# batteryholder2S3P_revC.net
KiCad netlist of a schematic drawn in EAGLE
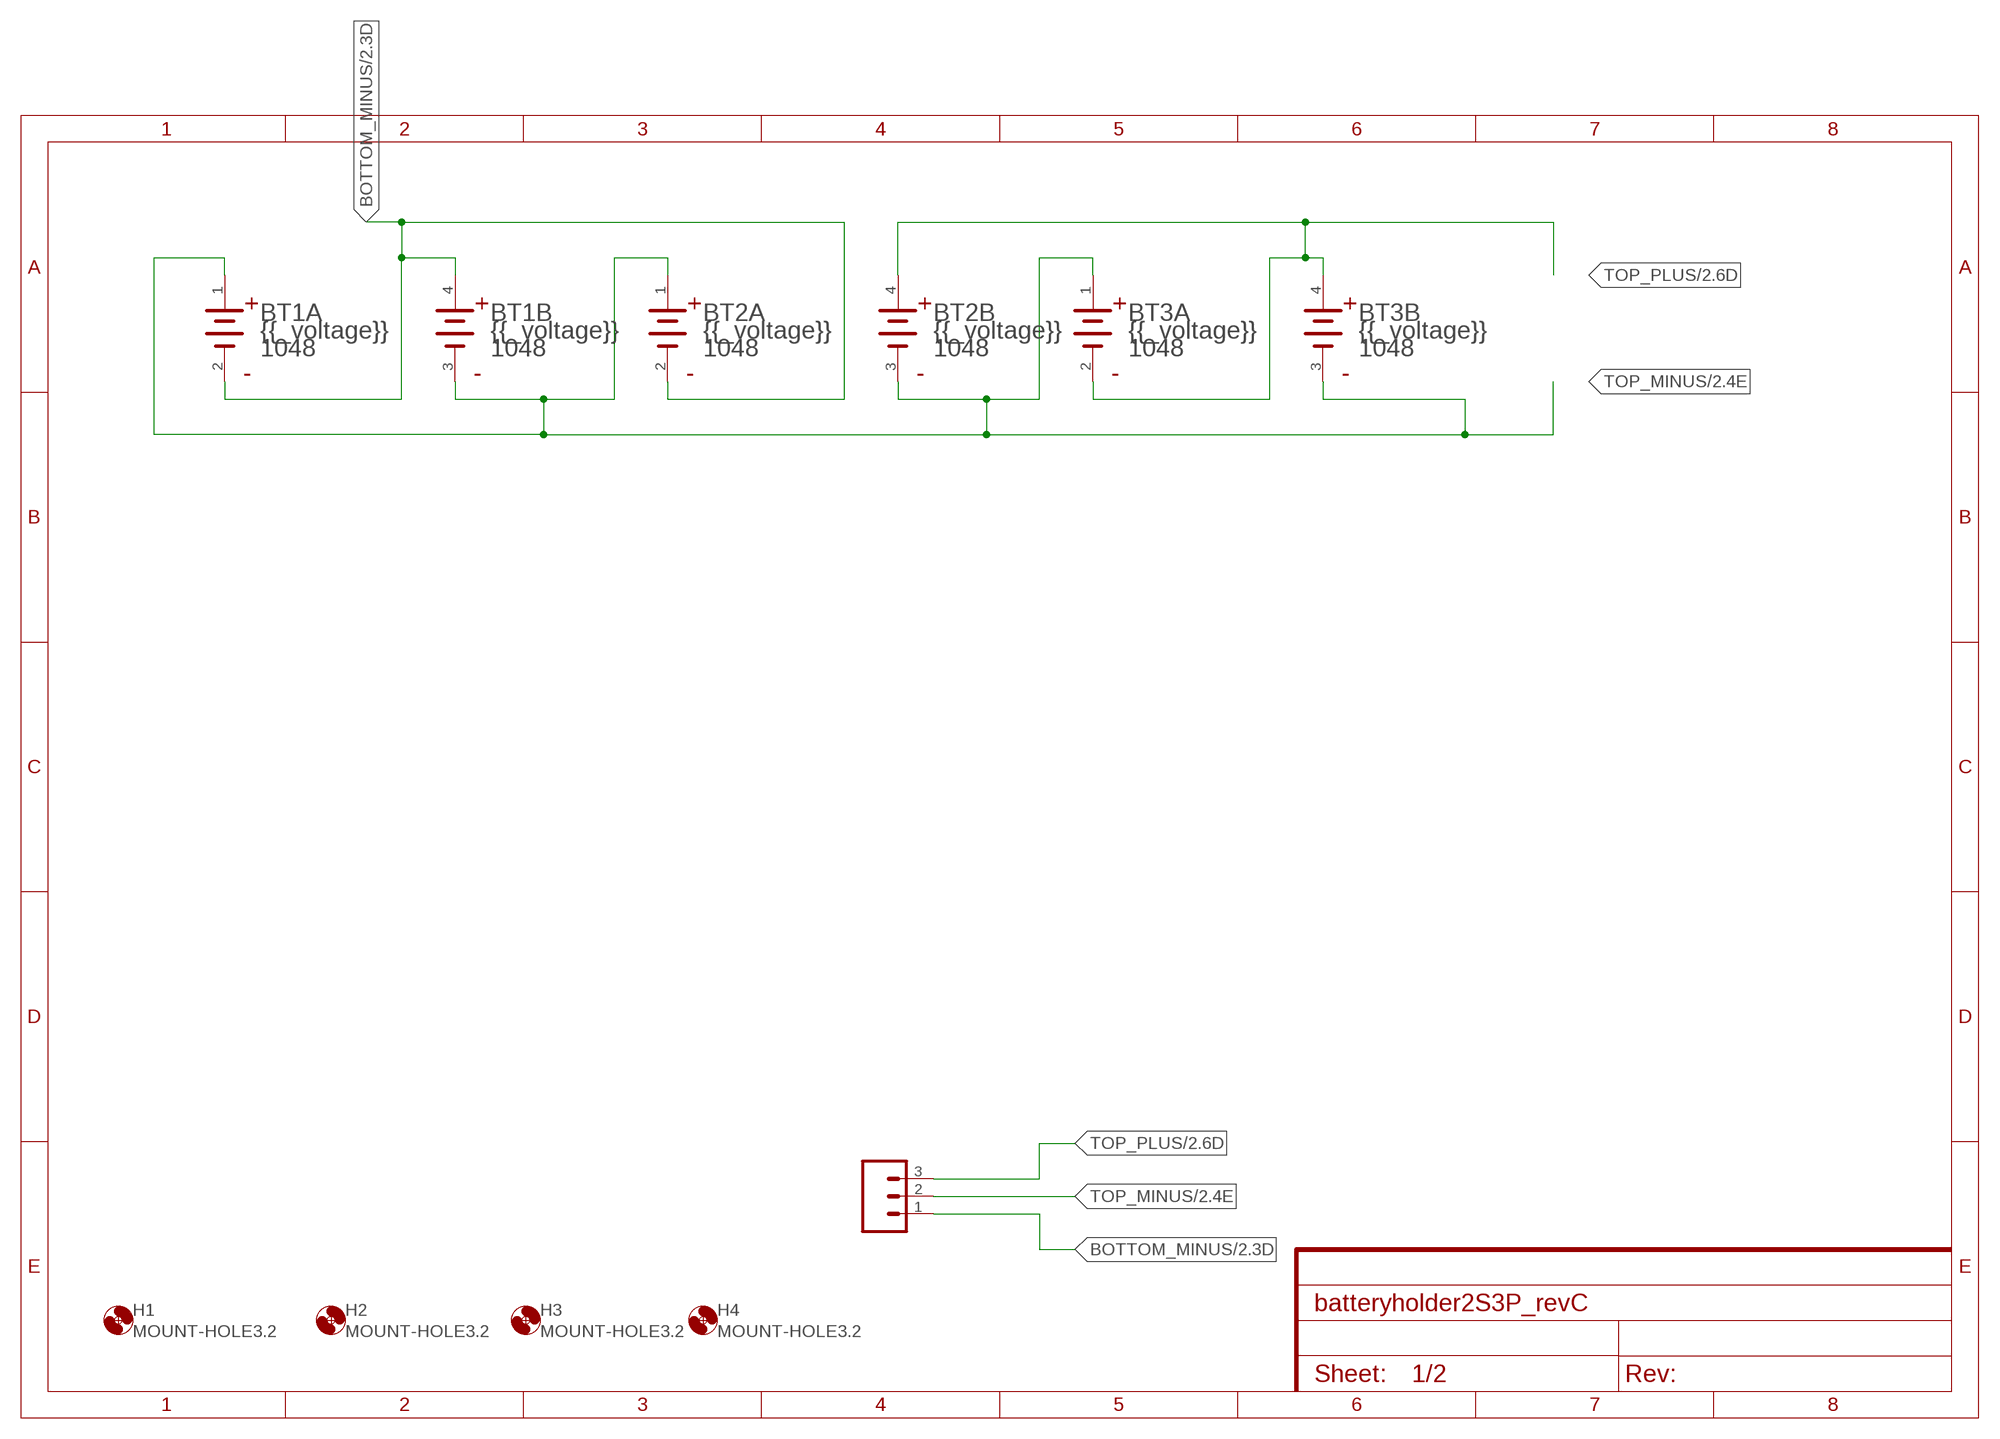
[diagram p0: schematic, sheet 1]
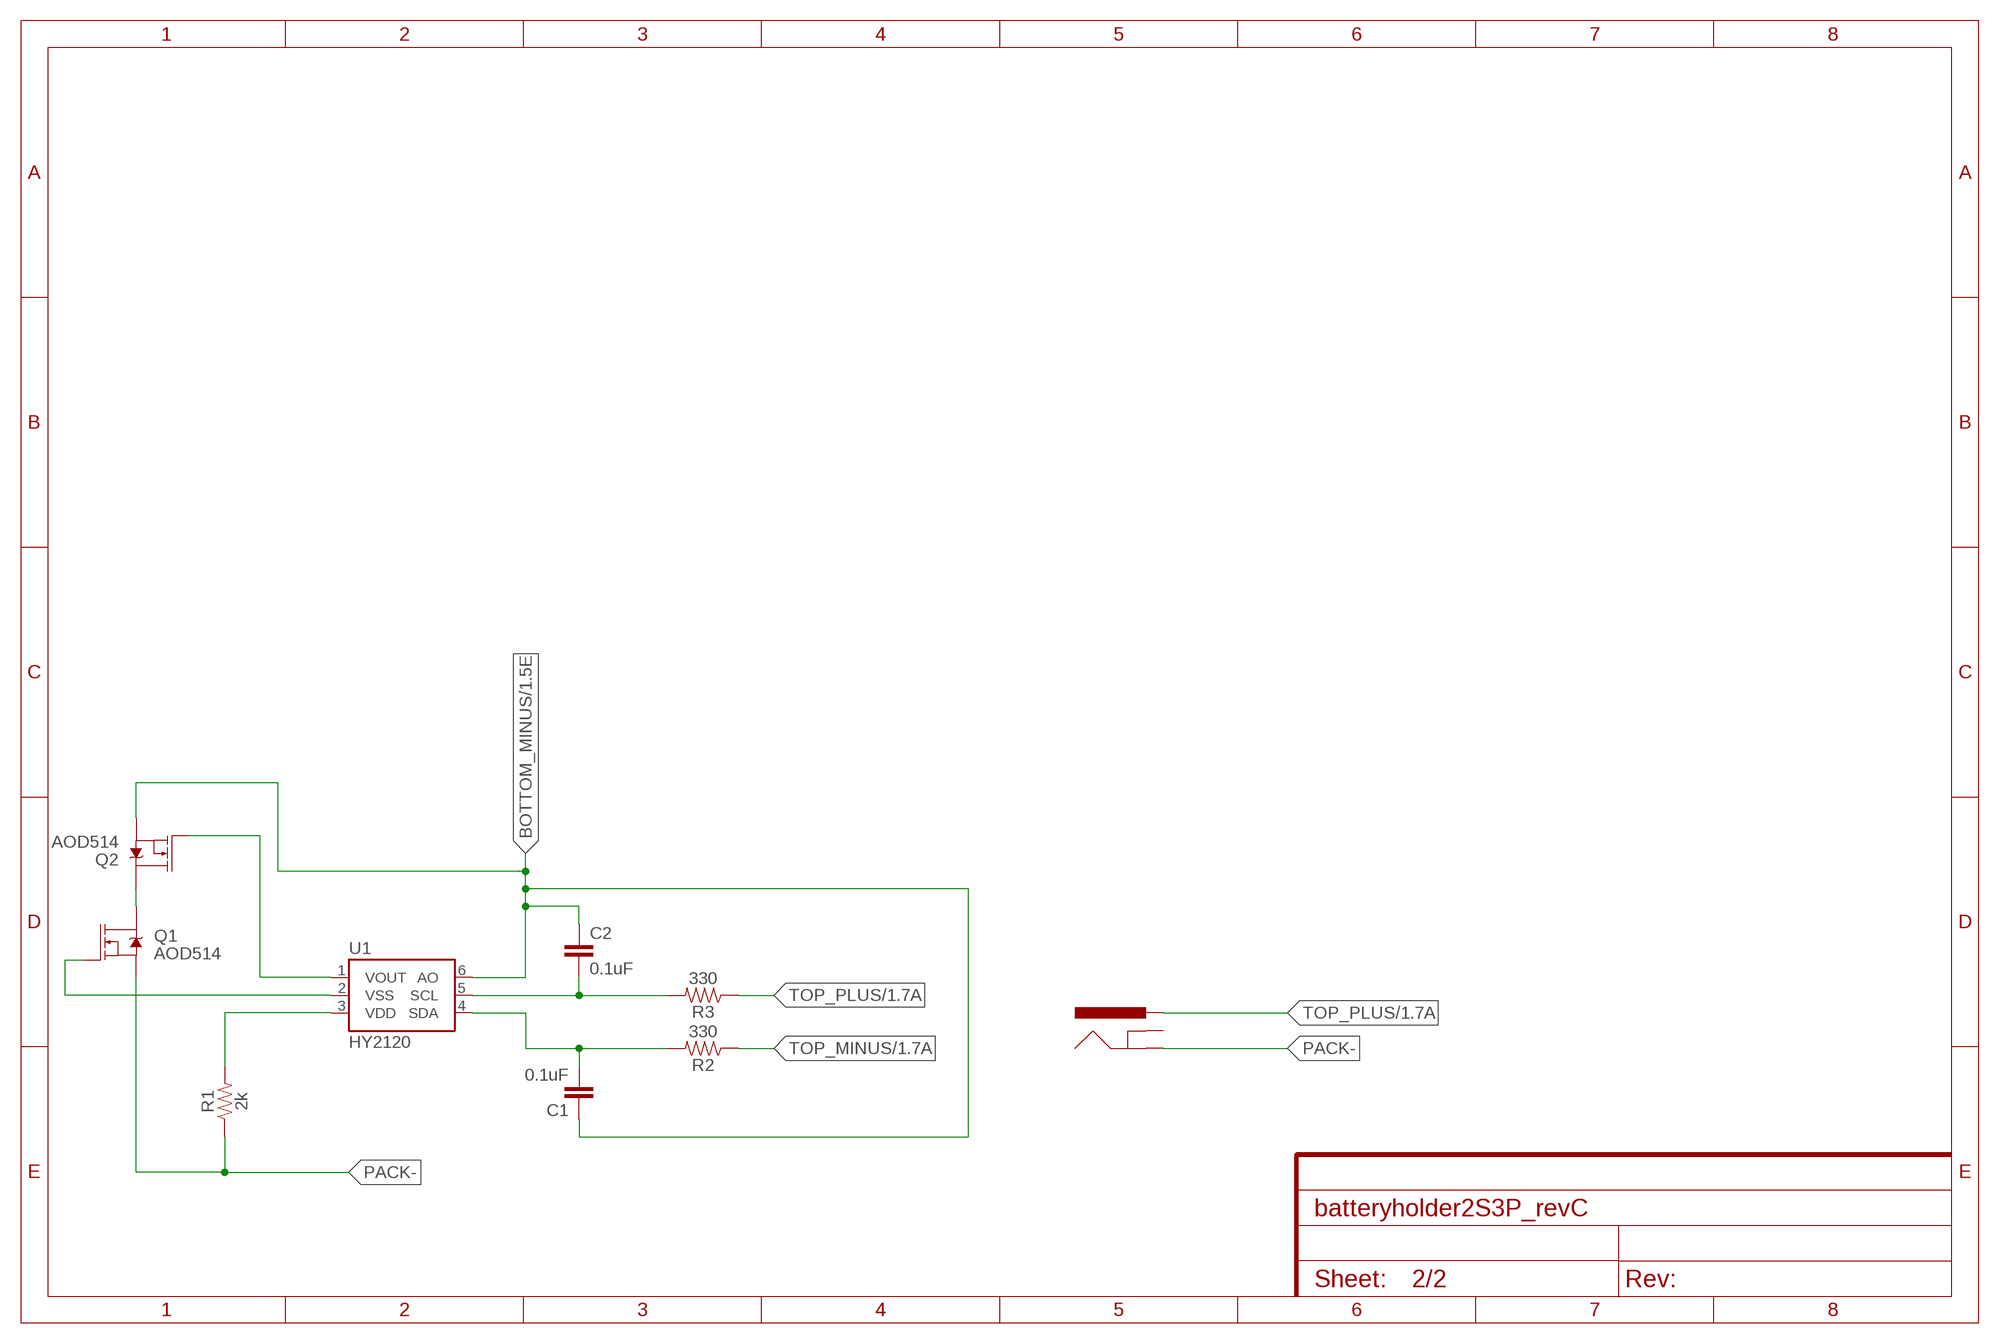
[diagram p1: schematic, sheet 2]

(export (version "E")
  (design (tool "Eeschema 10.0.6"))
  (components
    (comp (ref "C1")
      (value "0.1uF")
      (footprint "eagle-import:1206")
      (libsource (lib "eagle-import") (part "1.0UF-1206-50V-10%"))
    )
    (comp (ref "C2")
      (value "0.1uF")
      (footprint "eagle-import:1206")
      (libsource (lib "eagle-import") (part "1.0UF-1206-50V-10%"))
    )
    (comp (ref "J2")
      (value "POWER_JACKPTH_BREAD")
      (footprint "eagle-import:POWER_JACK_PTH_BREAD")
      (libsource (lib "eagle-import") (part "POWER_JACKPTH_BREAD"))
    )
    (comp (ref "Q1")
      (value "AOD514")
      (footprint "eagle-import:DPAK")
      (libsource (lib "eagle-import") (part "MOSFET-NCH-FDD8780"))
    )
    (comp (ref "Q2")
      (value "AOD514")
      (footprint "eagle-import:DPAK")
      (libsource (lib "eagle-import") (part "MOSFET-NCH-FDD8780"))
    )
    (comp (ref "R1")
      (value "2k")
      (footprint "eagle-import:1206")
      (libsource (lib "eagle-import") (part "RESISTOR1206"))
    )
    (comp (ref "R2")
      (value "330")
      (footprint "eagle-import:1206")
      (libsource (lib "eagle-import") (part "RESISTOR1206"))
    )
    (comp (ref "R3")
      (value "330")
      (footprint "eagle-import:1206")
      (libsource (lib "eagle-import") (part "RESISTOR1206"))
    )
    (comp (ref "U1")
      (value "HY2120")
      (footprint "eagle-import:SOT23-6")
      (libsource (lib "eagle-import") (part "MCP4725SOT-23"))
    )
    (comp (ref "BT1")
      (value "KEYSTONE_1048KEYSTONE_1048_0_0")
      (footprint "eagle-import:KEYSTONE_1048_0")
      (fields
        (field (name "DIGIKEY_PART_NUMBER") "36-1048-ND")
        (field (name "MF") "Keystone")
        (field (name "MOUSER_PART_NUMBER") "534-1048")
      )
      (libsource (lib "eagle-import") (part "KEYSTONE_1048KEYSTONE_1048_0_0"))
    )
    (comp (ref "BT2")
      (value "KEYSTONE_1048KEYSTONE_1048_0_0")
      (footprint "eagle-import:KEYSTONE_1048_0")
      (fields
        (field (name "DIGIKEY_PART_NUMBER") "36-1048-ND")
        (field (name "MF") "Keystone")
        (field (name "MOUSER_PART_NUMBER") "534-1048")
      )
      (libsource (lib "eagle-import") (part "KEYSTONE_1048KEYSTONE_1048_0_0"))
    )
    (comp (ref "BT3")
      (value "KEYSTONE_1048KEYSTONE_1048_0_0")
      (footprint "eagle-import:KEYSTONE_1048_0")
      (fields
        (field (name "DIGIKEY_PART_NUMBER") "36-1048-ND")
        (field (name "MF") "Keystone")
        (field (name "MOUSER_PART_NUMBER") "534-1048")
      )
      (libsource (lib "eagle-import") (part "KEYSTONE_1048KEYSTONE_1048_0_0"))
    )
    (comp (ref "H1")
      (value "MOUNT-HOLE3.2")
      (footprint "eagle-import:3,2")
      (libsource (lib "eagle-import") (part "MOUNT-HOLE3.2"))
    )
    (comp (ref "H2")
      (value "MOUNT-HOLE3.2")
      (footprint "eagle-import:3,2")
      (libsource (lib "eagle-import") (part "MOUNT-HOLE3.2"))
    )
    (comp (ref "H3")
      (value "MOUNT-HOLE3.2")
      (footprint "eagle-import:3,2")
      (libsource (lib "eagle-import") (part "MOUNT-HOLE3.2"))
    )
    (comp (ref "H4")
      (value "MOUNT-HOLE3.2")
      (footprint "eagle-import:3,2")
      (libsource (lib "eagle-import") (part "MOUNT-HOLE3.2"))
    )
    (comp (ref "J1")
      (value "CONN_03-SCREW-5MM")
      (footprint "eagle-import:SCREWTERMINAL-5MM-3")
      (libsource (lib "eagle-import") (part "CONN_03-SCREW-5MM"))
    )
  )
  (nets
    (net (code "1") (name "BOTTOM_MINUS") (class "Default")
      (node (ref "BT1") (pin "2") (pinfunction "1_CATHODE_2") (pintype "passive"))
      (node (ref "BT1") (pin "4") (pinfunction "2_ANODE_4") (pintype "passive"))
      (node (ref "BT2") (pin "2") (pinfunction "1_CATHODE_2") (pintype "passive"))
      (node (ref "C1") (pin "1") (pinfunction "1_1") (pintype "passive"))
      (node (ref "C2") (pin "1") (pinfunction "1_1") (pintype "passive"))
      (node (ref "J1") (pin "1") (pinfunction "1_1") (pintype "passive"))
      (node (ref "Q2") (pin "3") (pinfunction "S_3") (pintype "bidirectional"))
      (node (ref "U1") (pin "6") (pinfunction "AO_6") (pintype "bidirectional"))
    )
    (net (code "2") (name "Net-(Q1-D)") (class "Default")
      (node (ref "Q1") (pin "4") (pinfunction "D_4") (pintype "bidirectional"))
      (node (ref "Q2") (pin "4") (pinfunction "D_4") (pintype "bidirectional"))
    )
    (net (code "3") (name "Net-(Q1-G)") (class "Default")
      (node (ref "Q1") (pin "1") (pinfunction "G_1") (pintype "bidirectional"))
      (node (ref "U1") (pin "2") (pinfunction "VSS_2") (pintype "bidirectional"))
    )
    (net (code "4") (name "Net-(Q2-G)") (class "Default")
      (node (ref "Q2") (pin "1") (pinfunction "G_1") (pintype "bidirectional"))
      (node (ref "U1") (pin "1") (pinfunction "VOUT_1") (pintype "bidirectional"))
    )
    (net (code "5") (name "Net-(U1-SCL)") (class "Default")
      (node (ref "C2") (pin "2") (pinfunction "2_2") (pintype "passive"))
      (node (ref "R3") (pin "2") (pinfunction "2_2") (pintype "passive"))
      (node (ref "U1") (pin "5") (pinfunction "SCL_5") (pintype "bidirectional"))
    )
    (net (code "6") (name "Net-(U1-SDA)") (class "Default")
      (node (ref "C1") (pin "2") (pinfunction "2_2") (pintype "passive"))
      (node (ref "R2") (pin "2") (pinfunction "2_2") (pintype "passive"))
      (node (ref "U1") (pin "4") (pinfunction "SDA_4") (pintype "bidirectional"))
    )
    (net (code "7") (name "Net-(U1-VDD)") (class "Default")
      (node (ref "R1") (pin "2") (pinfunction "2_2") (pintype "passive"))
      (node (ref "U1") (pin "3") (pinfunction "VDD_3") (pintype "bidirectional"))
    )
    (net (code "8") (name "PACK-") (class "Default")
      (node (ref "J2") (pin "GND") (pinfunction "GND_GND") (pintype "bidirectional"))
      (node (ref "Q1") (pin "3") (pinfunction "S_3") (pintype "bidirectional"))
      (node (ref "R1") (pin "1") (pinfunction "1_1") (pintype "passive"))
    )
    (net (code "9") (name "TOP_MINUS") (class "Default")
      (node (ref "BT1") (pin "1") (pinfunction "1_ANODE_1") (pintype "passive"))
      (node (ref "BT1") (pin "3") (pinfunction "2_CATHODE_3") (pintype "passive"))
      (node (ref "BT2") (pin "1") (pinfunction "1_ANODE_1") (pintype "passive"))
      (node (ref "BT2") (pin "3") (pinfunction "2_CATHODE_3") (pintype "passive"))
      (node (ref "BT3") (pin "1") (pinfunction "1_ANODE_1") (pintype "passive"))
      (node (ref "BT3") (pin "3") (pinfunction "2_CATHODE_3") (pintype "passive"))
      (node (ref "J1") (pin "2") (pinfunction "2_2") (pintype "passive"))
      (node (ref "R2") (pin "1") (pinfunction "1_1") (pintype "passive"))
    )
    (net (code "10") (name "TOP_PLUS") (class "Default")
      (node (ref "BT2") (pin "4") (pinfunction "2_ANODE_4") (pintype "passive"))
      (node (ref "BT3") (pin "2") (pinfunction "1_CATHODE_2") (pintype "passive"))
      (node (ref "BT3") (pin "4") (pinfunction "2_ANODE_4") (pintype "passive"))
      (node (ref "J1") (pin "3") (pinfunction "3_3") (pintype "passive"))
      (node (ref "J2") (pin "PWR") (pinfunction "PWR_PWR") (pintype "bidirectional"))
      (node (ref "R3") (pin "1") (pinfunction "1_1") (pintype "passive"))
    )
    (net (code "11") (name "unconnected-(J2-PadGNDBREAK)") (class "Default")
      (node (ref "J2") (pin "GNDBREAK") (pinfunction "GNDBREAK_GNDBREAK") (pintype "bidirectional"))
    )
  )
)
